# 5_TTY.net
KiCad netlist of a schematic drawn in EAGLE
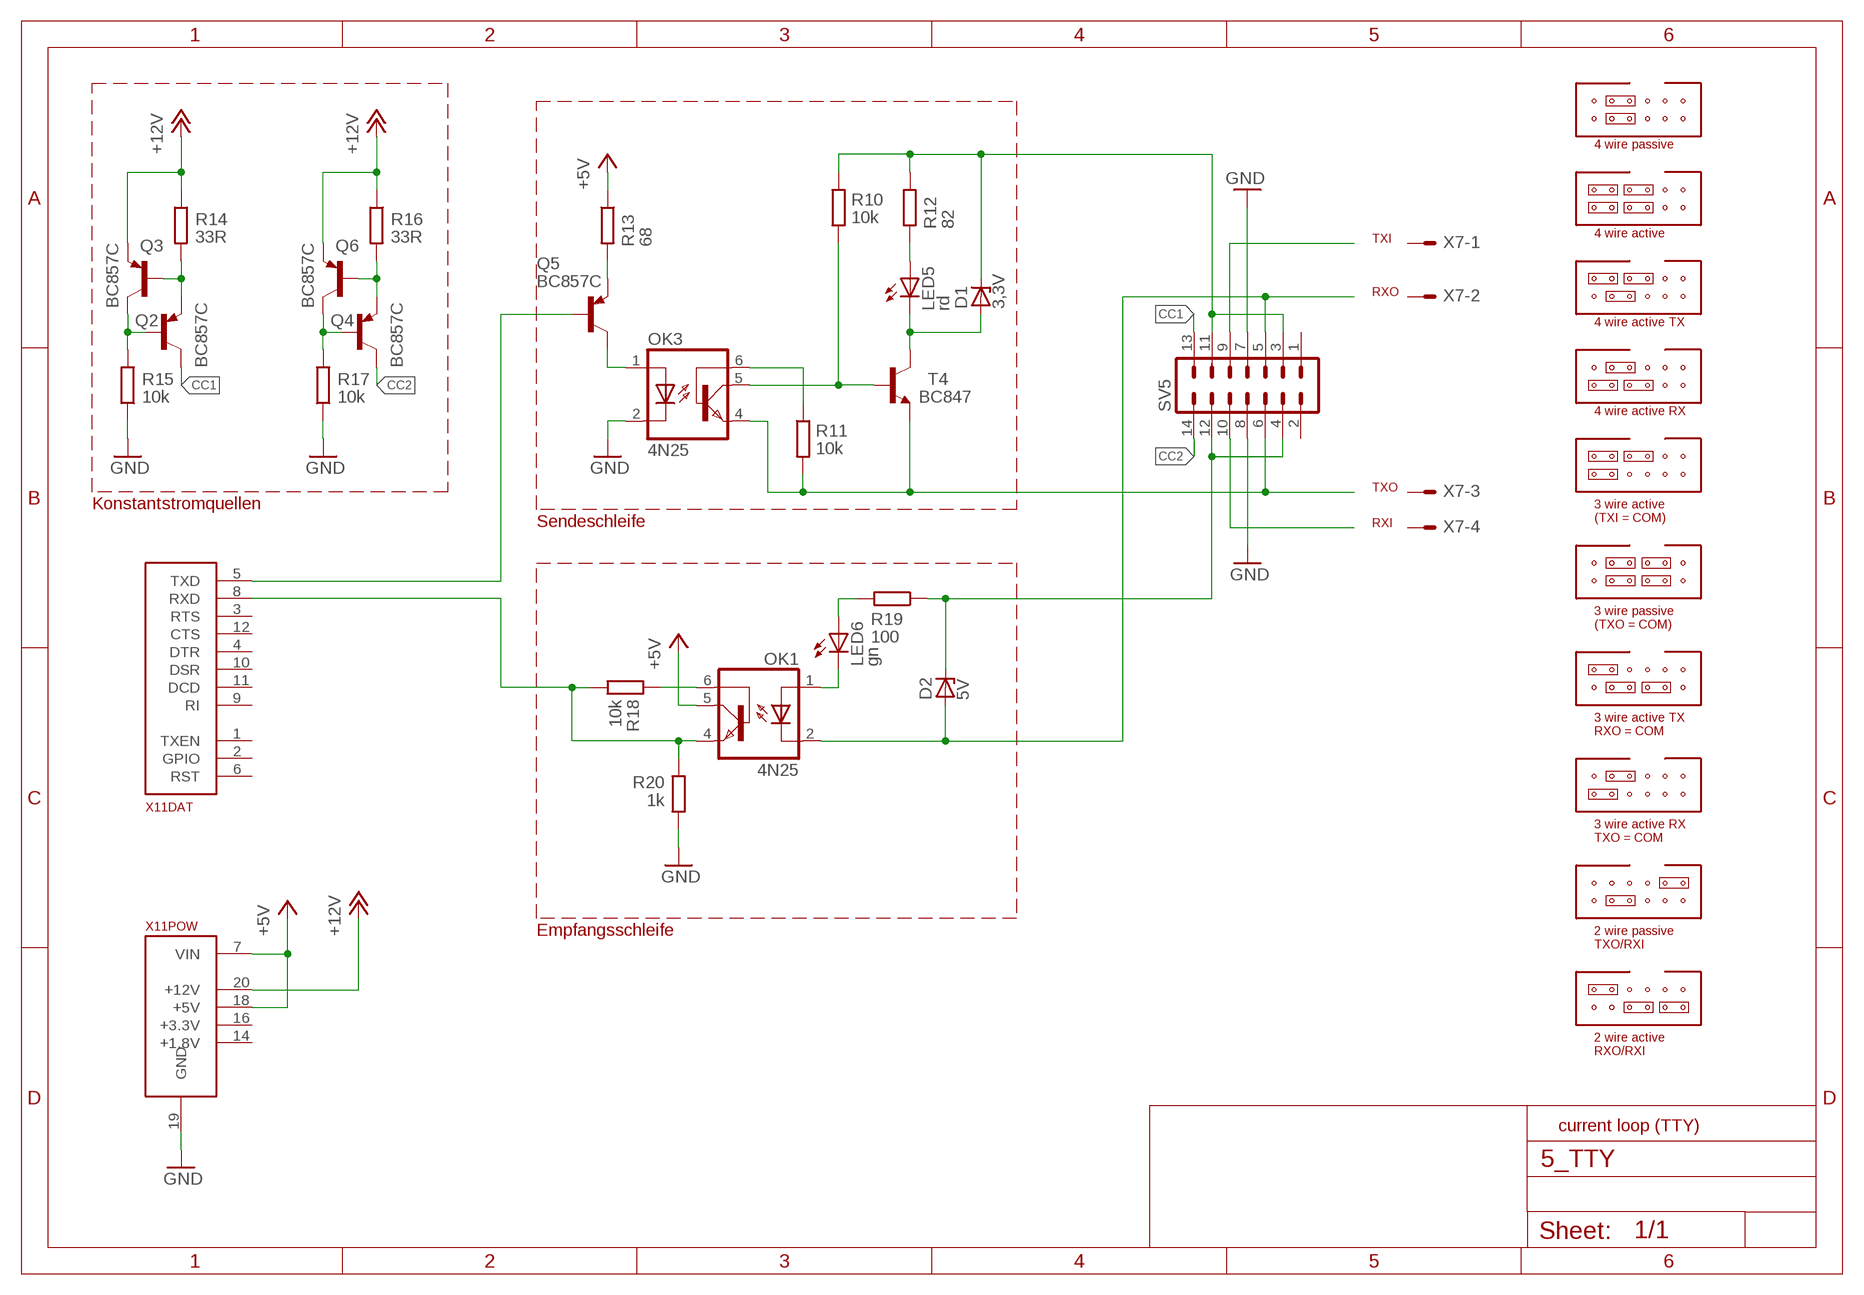
[diagram p0: schematic, sheet 1]

(export (version "E")
  (design (tool "Eeschema 10.0.6"))
  (components
    (comp (ref "D1")
      (value "3,3V")
      (footprint "eagle-import:SOT23")
      (libsource (lib "eagle-import") (part "ZENER-DIODESOT23"))
    )
    (comp (ref "D2")
      (value "5V")
      (footprint "eagle-import:SOT23")
      (libsource (lib "eagle-import") (part "ZENER-DIODESOT23"))
    )
    (comp (ref "LED5")
      (value "rd")
      (footprint "eagle-import:CHIPLED_0603")
      (libsource (lib "eagle-import") (part "LEDCHIPLED_0603"))
    )
    (comp (ref "LED6")
      (value "gn")
      (footprint "eagle-import:CHIPLED_0603")
      (libsource (lib "eagle-import") (part "LEDCHIPLED_0603"))
    )
    (comp (ref "OK1")
      (value "4N25")
      (footprint "eagle-import:DIL06")
      (fields (field (name "MF") "FAIRCHILD SEMICONDUCTOR") (field (name "MPN") "4N35"))
      (libsource (lib "eagle-import") (part "4N35"))
    )
    (comp (ref "OK3")
      (value "4N25")
      (footprint "eagle-import:DIL06")
      (fields (field (name "MF") "FAIRCHILD SEMICONDUCTOR") (field (name "MPN") "4N35"))
      (libsource (lib "eagle-import") (part "4N35"))
    )
    (comp (ref "Q2")
      (value "BC857C")
      (footprint "eagle-import:SOT23-BEC")
      (libsource (lib "eagle-import") (part "BC857SMDC"))
    )
    (comp (ref "Q3")
      (value "BC857C")
      (footprint "eagle-import:SOT23-BEC")
      (libsource (lib "eagle-import") (part "BC857SMDC"))
    )
    (comp (ref "Q4")
      (value "BC857C")
      (footprint "eagle-import:SOT23-BEC")
      (libsource (lib "eagle-import") (part "BC857SMDC"))
    )
    (comp (ref "Q5")
      (value "BC857C")
      (footprint "eagle-import:SOT23-BEC")
      (libsource (lib "eagle-import") (part "BC857SMDC"))
    )
    (comp (ref "Q6")
      (value "BC857C")
      (footprint "eagle-import:SOT23-BEC")
      (libsource (lib "eagle-import") (part "BC857SMDC"))
    )
    (comp (ref "R10")
      (value "10k")
      (footprint "eagle-import:R0805")
      (libsource (lib "eagle-import") (part "R-EU_R0805"))
    )
    (comp (ref "R11")
      (value "10k")
      (footprint "eagle-import:R0805")
      (libsource (lib "eagle-import") (part "R-EU_R0805"))
    )
    (comp (ref "R12")
      (value "82")
      (footprint "eagle-import:R0805")
      (libsource (lib "eagle-import") (part "R-EU_R0805"))
    )
    (comp (ref "R13")
      (value "68")
      (footprint "eagle-import:R0805")
      (libsource (lib "eagle-import") (part "R-EU_R0805"))
    )
    (comp (ref "R14")
      (value "33R")
      (footprint "eagle-import:R0805")
      (libsource (lib "eagle-import") (part "R-EU_R0805"))
    )
    (comp (ref "R15")
      (value "10k")
      (footprint "eagle-import:R0805")
      (libsource (lib "eagle-import") (part "R-EU_R0805"))
    )
    (comp (ref "R16")
      (value "33R")
      (footprint "eagle-import:R0805")
      (libsource (lib "eagle-import") (part "R-EU_R0805"))
    )
    (comp (ref "R17")
      (value "10k")
      (footprint "eagle-import:R0805")
      (libsource (lib "eagle-import") (part "R-EU_R0805"))
    )
    (comp (ref "R18")
      (value "10k")
      (footprint "eagle-import:R0805")
      (libsource (lib "eagle-import") (part "R-EU_R0805"))
    )
    (comp (ref "R19")
      (value "100")
      (footprint "eagle-import:R0805")
      (libsource (lib "eagle-import") (part "R-EU_R0805"))
    )
    (comp (ref "R20")
      (value "1k")
      (footprint "eagle-import:R0805")
      (libsource (lib "eagle-import") (part "R-EU_R0805"))
    )
    (comp (ref "SV5")
      (value "ML14L")
      (footprint "eagle-import:ML14L")
      (libsource (lib "eagle-import") (part "ML14L"))
    )
    (comp (ref "T4")
      (value "BC847")
      (footprint "eagle-import:SOT23")
      (libsource (lib "eagle-import") (part "BC847"))
    )
    (comp (ref "X7")
      (value "AKL18X-04W")
      (footprint "eagle-import:AKL182-04")
      (libsource (lib "eagle-import") (part "AKL18X-04W"))
    )
    (comp (ref "X11")
      (value "ALLSERIALD")
      (footprint "eagle-import:DAUGHTER-THT")
      (libsource (lib "eagle-import") (part "ALLSERIALD"))
    )
  )
  (nets
    (net (code "1") (name "+5V") (class "Default")
      (node (ref "OK1") (pin "5") (pinfunction "COL_5") (pintype "passive"))
      (node (ref "R13") (pin "1") (pinfunction "1_1") (pintype "passive"))
      (node (ref "X11") (pin "18") (pinfunction "+5V_18") (pintype "bidirectional"))
      (node (ref "X11") (pin "7") (pinfunction "VIN_7") (pintype "bidirectional"))
    )
    (net (code "2") (name "+12V") (class "Default")
      (node (ref "Q3") (pin "E") (pinfunction "E_E") (pintype "passive"))
      (node (ref "Q6") (pin "E") (pinfunction "E_E") (pintype "passive"))
      (node (ref "R14") (pin "1") (pinfunction "1_1") (pintype "passive"))
      (node (ref "R16") (pin "1") (pinfunction "1_1") (pintype "passive"))
      (node (ref "X11") (pin "20") (pinfunction "+12V_20") (pintype "bidirectional"))
    )
    (net (code "3") (name "CC1") (class "Default")
      (node (ref "Q2") (pin "C") (pinfunction "C_C") (pintype "passive"))
      (node (ref "SV5") (pin "13") (pinfunction "13_13") (pintype "passive"))
    )
    (net (code "4") (name "CC2") (class "Default")
      (node (ref "Q4") (pin "C") (pinfunction "C_C") (pintype "passive"))
      (node (ref "SV5") (pin "14") (pinfunction "14_14") (pintype "passive"))
    )
    (net (code "5") (name "GND") (class "Default")
      (node (ref "OK3") (pin "2") (pinfunction "C_2") (pintype "passive"))
      (node (ref "R15") (pin "1") (pinfunction "1_1") (pintype "passive"))
      (node (ref "R17") (pin "1") (pinfunction "1_1") (pintype "passive"))
      (node (ref "R20") (pin "1") (pinfunction "1_1") (pintype "passive"))
      (node (ref "SV5") (pin "7") (pinfunction "7_7") (pintype "passive"))
      (node (ref "SV5") (pin "8") (pinfunction "8_8") (pintype "passive"))
      (node (ref "X11") (pin "19") (pinfunction "GND_19") (pintype "bidirectional"))
    )
    (net (code "6") (name "Net-(D1-A)") (class "Default")
      (node (ref "D1") (pin "1") (pinfunction "A_1") (pintype "passive"))
      (node (ref "LED5") (pin "C") (pinfunction "C_C") (pintype "passive"))
      (node (ref "T4") (pin "3") (pinfunction "C_3") (pintype "passive"))
    )
    (net (code "7") (name "Net-(D1-C)") (class "Default")
      (node (ref "D1") (pin "3") (pinfunction "C_3") (pintype "passive"))
      (node (ref "R10") (pin "1") (pinfunction "1_1") (pintype "passive"))
      (node (ref "R12") (pin "1") (pinfunction "1_1") (pintype "passive"))
      (node (ref "SV5") (pin "11") (pinfunction "11_11") (pintype "passive"))
      (node (ref "SV5") (pin "3") (pinfunction "3_3") (pintype "passive"))
    )
    (net (code "8") (name "Net-(D2-A)") (class "Default")
      (node (ref "D2") (pin "1") (pinfunction "A_1") (pintype "passive"))
      (node (ref "OK1") (pin "2") (pinfunction "C_2") (pintype "passive"))
      (node (ref "SV5") (pin "5") (pinfunction "5_5") (pintype "passive"))
    )
    (net (code "9") (name "Net-(D2-C)") (class "Default")
      (node (ref "D2") (pin "3") (pinfunction "C_3") (pintype "passive"))
      (node (ref "R19") (pin "1") (pinfunction "1_1") (pintype "passive"))
      (node (ref "SV5") (pin "12") (pinfunction "12_12") (pintype "passive"))
      (node (ref "SV5") (pin "4") (pinfunction "4_4") (pintype "passive"))
    )
    (net (code "10") (name "Net-(LED5-PadA)") (class "Default")
      (node (ref "LED5") (pin "A") (pinfunction "A_A") (pintype "passive"))
      (node (ref "R12") (pin "2") (pinfunction "2_2") (pintype "passive"))
    )
    (net (code "11") (name "Net-(LED6-PadA)") (class "Default")
      (node (ref "LED6") (pin "A") (pinfunction "A_A") (pintype "passive"))
      (node (ref "R19") (pin "2") (pinfunction "2_2") (pintype "passive"))
    )
    (net (code "12") (name "Net-(OK1-A)") (class "Default")
      (node (ref "LED6") (pin "C") (pinfunction "C_C") (pintype "passive"))
      (node (ref "OK1") (pin "1") (pinfunction "A_1") (pintype "passive"))
    )
    (net (code "13") (name "Net-(OK1-BAS)") (class "Default")
      (node (ref "OK1") (pin "6") (pinfunction "BAS_6") (pintype "passive"))
      (node (ref "R18") (pin "1") (pinfunction "1_1") (pintype "passive"))
    )
    (net (code "14") (name "Net-(OK1-EMI)") (class "Default")
      (node (ref "OK1") (pin "4") (pinfunction "EMI_4") (pintype "passive"))
      (node (ref "R18") (pin "2") (pinfunction "2_2") (pintype "passive"))
      (node (ref "R20") (pin "2") (pinfunction "2_2") (pintype "passive"))
      (node (ref "X11") (pin "8") (pinfunction "RXD_8") (pintype "bidirectional"))
    )
    (net (code "15") (name "Net-(OK3-A)") (class "Default")
      (node (ref "OK3") (pin "1") (pinfunction "A_1") (pintype "passive"))
      (node (ref "Q5") (pin "C") (pinfunction "C_C") (pintype "passive"))
    )
    (net (code "16") (name "Net-(OK3-BAS)") (class "Default")
      (node (ref "OK3") (pin "6") (pinfunction "BAS_6") (pintype "passive"))
      (node (ref "R11") (pin "1") (pinfunction "1_1") (pintype "passive"))
    )
    (net (code "17") (name "Net-(OK3-COL)") (class "Default")
      (node (ref "OK3") (pin "5") (pinfunction "COL_5") (pintype "passive"))
      (node (ref "R10") (pin "2") (pinfunction "2_2") (pintype "passive"))
      (node (ref "T4") (pin "1") (pinfunction "B_1") (pintype "passive"))
    )
    (net (code "18") (name "Net-(OK3-EMI)") (class "Default")
      (node (ref "OK3") (pin "4") (pinfunction "EMI_4") (pintype "passive"))
      (node (ref "R11") (pin "2") (pinfunction "2_2") (pintype "passive"))
      (node (ref "SV5") (pin "6") (pinfunction "6_6") (pintype "passive"))
      (node (ref "T4") (pin "2") (pinfunction "E_2") (pintype "passive"))
    )
    (net (code "19") (name "Net-(Q2-PadB)") (class "Default")
      (node (ref "Q2") (pin "B") (pinfunction "B_B") (pintype "passive"))
      (node (ref "Q3") (pin "C") (pinfunction "C_C") (pintype "passive"))
      (node (ref "R15") (pin "2") (pinfunction "2_2") (pintype "passive"))
    )
    (net (code "20") (name "Net-(Q2-PadE)") (class "Default")
      (node (ref "Q2") (pin "E") (pinfunction "E_E") (pintype "passive"))
      (node (ref "Q3") (pin "B") (pinfunction "B_B") (pintype "passive"))
      (node (ref "R14") (pin "2") (pinfunction "2_2") (pintype "passive"))
    )
    (net (code "21") (name "Net-(Q4-PadB)") (class "Default")
      (node (ref "Q4") (pin "B") (pinfunction "B_B") (pintype "passive"))
      (node (ref "Q6") (pin "C") (pinfunction "C_C") (pintype "passive"))
      (node (ref "R17") (pin "2") (pinfunction "2_2") (pintype "passive"))
    )
    (net (code "22") (name "Net-(Q4-PadE)") (class "Default")
      (node (ref "Q4") (pin "E") (pinfunction "E_E") (pintype "passive"))
      (node (ref "Q6") (pin "B") (pinfunction "B_B") (pintype "passive"))
      (node (ref "R16") (pin "2") (pinfunction "2_2") (pintype "passive"))
    )
    (net (code "23") (name "Net-(Q5-PadE)") (class "Default")
      (node (ref "Q5") (pin "E") (pinfunction "E_E") (pintype "passive"))
      (node (ref "R13") (pin "2") (pinfunction "2_2") (pintype "passive"))
    )
    (net (code "24") (name "Net-(X11A-TXD)") (class "Default")
      (node (ref "Q5") (pin "B") (pinfunction "B_B") (pintype "passive"))
      (node (ref "X11") (pin "5") (pinfunction "TXD_5") (pintype "bidirectional"))
    )
    (net (code "25") (name "unconnected-(SV5-Pad1)") (class "Default")
      (node (ref "SV5") (pin "1") (pinfunction "1_1") (pintype "passive"))
    )
    (net (code "26") (name "unconnected-(SV5-Pad2)") (class "Default")
      (node (ref "SV5") (pin "2") (pinfunction "2_2") (pintype "passive"))
    )
    (net (code "27") (name "unconnected-(SV5-Pad9)") (class "Default")
      (node (ref "SV5") (pin "9") (pinfunction "9_9") (pintype "passive"))
    )
    (net (code "28") (name "unconnected-(SV5-Pad10)") (class "Default")
      (node (ref "SV5") (pin "10") (pinfunction "10_10") (pintype "passive"))
    )
    (net (code "29") (name "unconnected-(X7A-S-PadP$1)") (class "Default")
      (node (ref "X7") (pin "P$1") (pinfunction "S_P$1") (pintype "passive"))
    )
    (net (code "30") (name "unconnected-(X7B-S-PadP$2)") (class "Default")
      (node (ref "X7") (pin "P$2") (pinfunction "S_P$2") (pintype "passive"))
    )
    (net (code "31") (name "unconnected-(X7C-S-PadP$3)") (class "Default")
      (node (ref "X7") (pin "P$3") (pinfunction "S_P$3") (pintype "passive"))
    )
    (net (code "32") (name "unconnected-(X7D-S-PadP$4)") (class "Default")
      (node (ref "X7") (pin "P$4") (pinfunction "S_P$4") (pintype "passive"))
    )
    (net (code "33") (name "unconnected-(X11A-CTS-Pad12)") (class "Default")
      (node (ref "X11") (pin "12") (pinfunction "CTS_12") (pintype "bidirectional"))
    )
    (net (code "34") (name "unconnected-(X11A-DCD-Pad11)") (class "Default")
      (node (ref "X11") (pin "11") (pinfunction "DCD_11") (pintype "bidirectional"))
    )
    (net (code "35") (name "unconnected-(X11A-DSR-Pad10)") (class "Default")
      (node (ref "X11") (pin "10") (pinfunction "DSR_10") (pintype "bidirectional"))
    )
    (net (code "36") (name "unconnected-(X11A-DTR-Pad4)") (class "Default")
      (node (ref "X11") (pin "4") (pinfunction "DTR_4") (pintype "bidirectional"))
    )
    (net (code "37") (name "unconnected-(X11A-GPIO-Pad2)") (class "Default")
      (node (ref "X11") (pin "2") (pinfunction "GPIO_2") (pintype "bidirectional"))
    )
    (net (code "38") (name "unconnected-(X11A-RI-Pad9)") (class "Default")
      (node (ref "X11") (pin "9") (pinfunction "RI_9") (pintype "bidirectional"))
    )
    (net (code "39") (name "unconnected-(X11A-RST-Pad6)") (class "Default")
      (node (ref "X11") (pin "6") (pinfunction "RST_6") (pintype "bidirectional"))
    )
    (net (code "40") (name "unconnected-(X11A-RTS-Pad3)") (class "Default")
      (node (ref "X11") (pin "3") (pinfunction "RTS_3") (pintype "bidirectional"))
    )
    (net (code "41") (name "unconnected-(X11A-TXEN-Pad1)") (class "Default")
      (node (ref "X11") (pin "1") (pinfunction "TXEN_1") (pintype "bidirectional"))
    )
    (net (code "42") (name "unconnected-(X11B-+1.8V-Pad14)") (class "Default")
      (node (ref "X11") (pin "14") (pinfunction "+1.8V_14") (pintype "bidirectional"))
    )
    (net (code "43") (name "unconnected-(X11B-+3.3V-Pad16)") (class "Default")
      (node (ref "X11") (pin "16") (pinfunction "+3.3V_16") (pintype "bidirectional"))
    )
  )
)
